# cascadence11.net
KiCad netlist of a schematic drawn in EAGLE
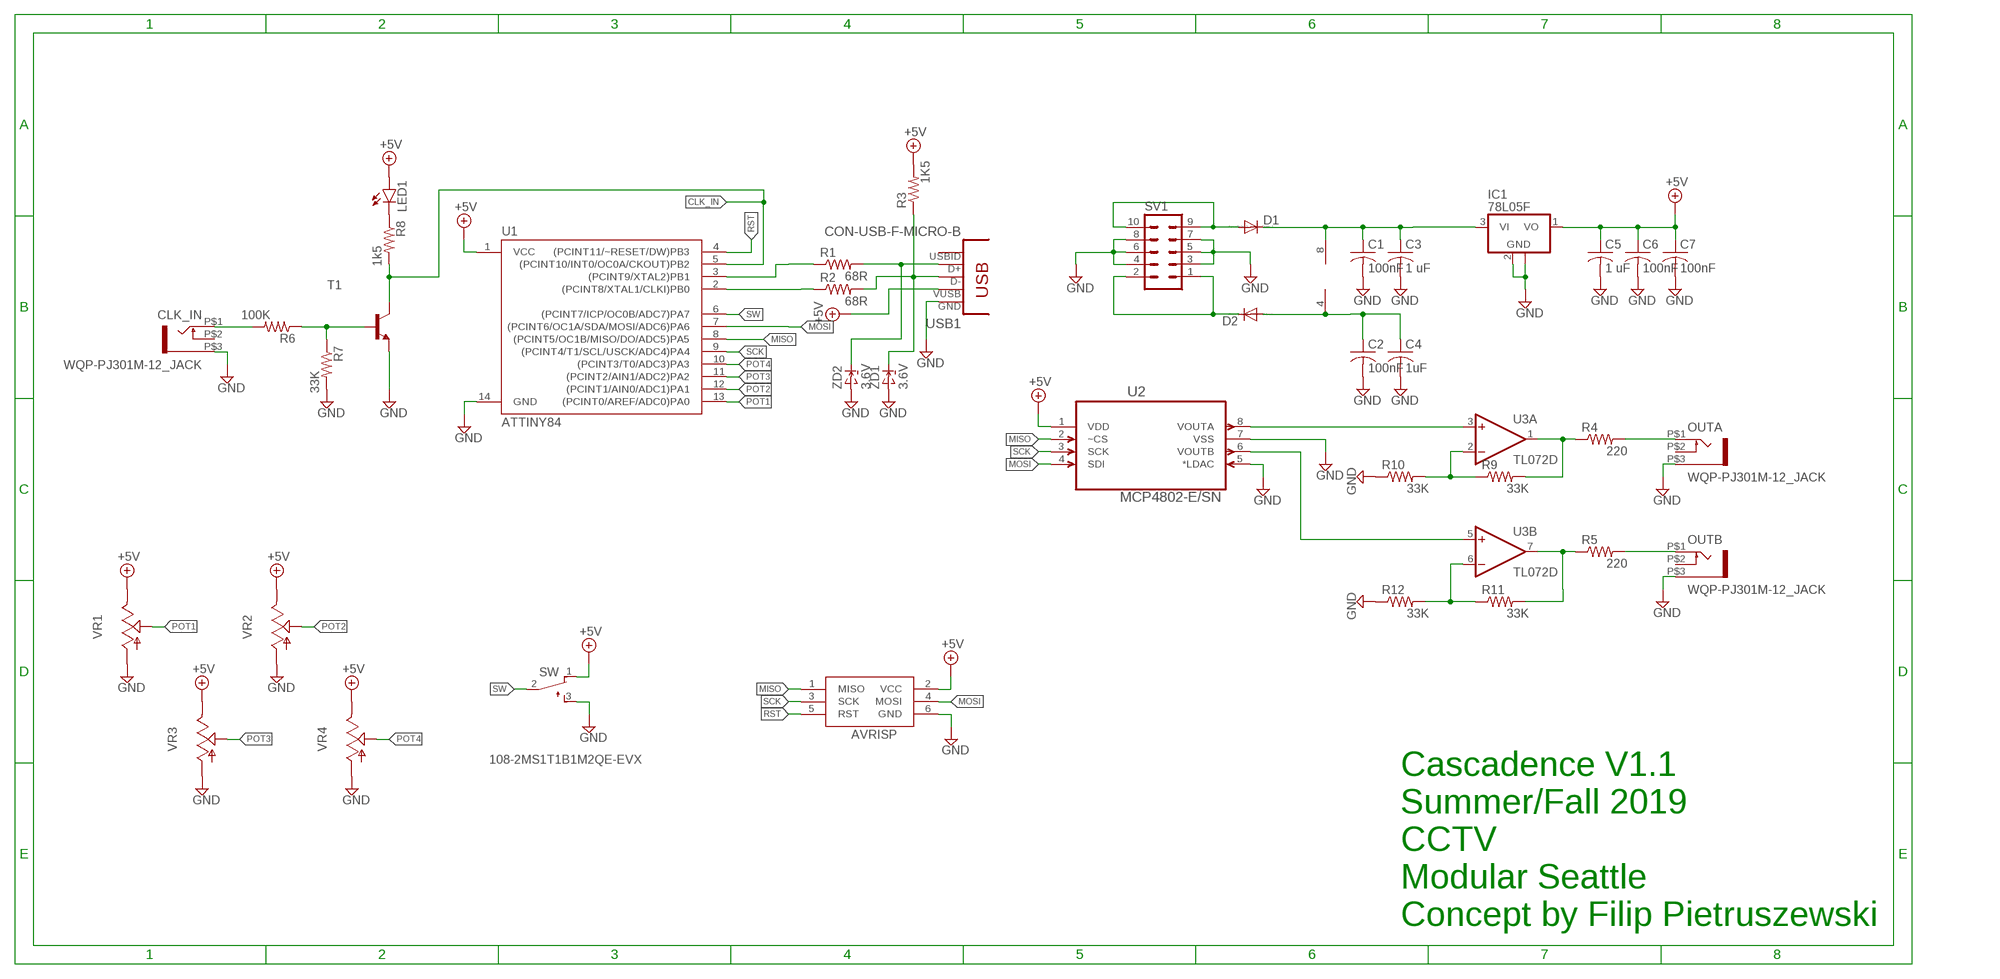
[diagram p0: schematic, sheet 1]

(export (version "E")
  (design (tool "Eeschema 10.0.6"))
  (components
    (comp (ref "AVRISP")
      (value "AVRISP-6")
      (footprint "eagle-import:AVRISP")
      (libsource (lib "eagle-import") (part "AVRISP-6"))
    )
    (comp (ref "C1")
      (value "100nF")
      (footprint "eagle-import:C0805K")
      (libsource (lib "eagle-import") (part "C-USC0805K"))
    )
    (comp (ref "C2")
      (value "100nF")
      (footprint "eagle-import:C0805K")
      (libsource (lib "eagle-import") (part "C-USC0805K"))
    )
    (comp (ref "C3")
      (value "1 uF")
      (footprint "eagle-import:C1206")
      (libsource (lib "eagle-import") (part "C-USC1206"))
    )
    (comp (ref "C4")
      (value "1uF")
      (footprint "eagle-import:C1206")
      (libsource (lib "eagle-import") (part "C-USC1206"))
    )
    (comp (ref "C5")
      (value "1 uF")
      (footprint "eagle-import:C1206")
      (libsource (lib "eagle-import") (part "C-USC1206"))
    )
    (comp (ref "C6")
      (value "100nF")
      (footprint "eagle-import:C0805K")
      (libsource (lib "eagle-import") (part "C-USC0805K"))
    )
    (comp (ref "C7")
      (value "100nF")
      (footprint "eagle-import:C0805K")
      (libsource (lib "eagle-import") (part "C-USC0805K"))
    )
    (comp (ref "CLK_IN")
      (value "WQP-PJ301M-12_JACK")
      (footprint "eagle-import:WQP-PJ301M-12_JACK")
      (libsource (lib "eagle-import") (part "WQP-PJ301M-12_JACK"))
    )
    (comp (ref "D1")
      (value "DIODE-SMB")
      (footprint "eagle-import:SMB")
      (libsource (lib "eagle-import") (part "DIODE-SMB"))
    )
    (comp (ref "D2")
      (value "DIODE-SMB")
      (footprint "eagle-import:SMB")
      (libsource (lib "eagle-import") (part "DIODE-SMB"))
    )
    (comp (ref "IC1")
      (value "78L05F")
      (footprint "eagle-import:SOT89")
      (libsource (lib "eagle-import") (part "78LF05"))
    )
    (comp (ref "LED1")
      (value "LED3MM")
      (footprint "eagle-import:LED3MM")
      (libsource (lib "eagle-import") (part "LED3MM"))
    )
    (comp (ref "OUTA")
      (value "WQP-PJ301M-12_JACK")
      (footprint "eagle-import:WQP-PJ301M-12_JACK")
      (libsource (lib "eagle-import") (part "WQP-PJ301M-12_JACK"))
    )
    (comp (ref "OUTB")
      (value "WQP-PJ301M-12_JACK")
      (footprint "eagle-import:WQP-PJ301M-12_JACK")
      (libsource (lib "eagle-import") (part "WQP-PJ301M-12_JACK"))
    )
    (comp (ref "R1")
      (value "68R")
      (footprint "eagle-import:R0805W")
      (libsource (lib "eagle-import") (part "R-US_R0805W"))
    )
    (comp (ref "R2")
      (value "68R")
      (footprint "eagle-import:R0805W")
      (libsource (lib "eagle-import") (part "R-US_R0805W"))
    )
    (comp (ref "R3")
      (value "1K5")
      (footprint "eagle-import:R0805W")
      (libsource (lib "eagle-import") (part "R-US_R0805W"))
    )
    (comp (ref "R4")
      (value "220")
      (footprint "eagle-import:R0805W")
      (libsource (lib "eagle-import") (part "R-US_R0805W"))
    )
    (comp (ref "R5")
      (value "220")
      (footprint "eagle-import:R0805W")
      (libsource (lib "eagle-import") (part "R-US_R0805W"))
    )
    (comp (ref "R6")
      (value "100K")
      (footprint "eagle-import:R0805W")
      (libsource (lib "eagle-import") (part "R-US_R0805W"))
    )
    (comp (ref "R7")
      (value "33K")
      (footprint "eagle-import:R0805W")
      (libsource (lib "eagle-import") (part "R-US_R0805W"))
    )
    (comp (ref "R8")
      (value "1k5")
      (footprint "eagle-import:R0805W")
      (libsource (lib "eagle-import") (part "R-US_R0805W"))
    )
    (comp (ref "R9")
      (value "33K")
      (footprint "eagle-import:R0805W")
      (libsource (lib "eagle-import") (part "R-US_R0805W"))
    )
    (comp (ref "R10")
      (value "33K")
      (footprint "eagle-import:R0805W")
      (libsource (lib "eagle-import") (part "R-US_R0805W"))
    )
    (comp (ref "R11")
      (value "33K")
      (footprint "eagle-import:R0805W")
      (libsource (lib "eagle-import") (part "R-US_R0805W"))
    )
    (comp (ref "R12")
      (value "33K")
      (footprint "eagle-import:R0805W")
      (libsource (lib "eagle-import") (part "R-US_R0805W"))
    )
    (comp (ref "SV1")
      (value "EURO_POWER_HEADERFAT_PADS")
      (footprint "eagle-import:EURO_PWR_HEADER_FAT")
      (libsource (lib "eagle-import") (part "EURO_POWER_HEADERFAT_PADS"))
    )
    (comp (ref "SW")
      (value "108-2MS1T1B1M2QE-EVX")
      (footprint "eagle-import:TL3XPO")
      (libsource (lib "eagle-import") (part "TL32PO"))
    )
    (comp (ref "T1")
      (value "MMBT3904LT1-NPN-SOT23-BEC")
      (footprint "eagle-import:SOT23-BEC")
      (libsource (lib "eagle-import") (part "-NPN-SOT23-BECMMBT3904LT1"))
    )
    (comp (ref "U1")
      (value "ATTINY84")
      (footprint "eagle-import:SO14")
      (libsource (lib "eagle-import") (part "ATTINY84"))
    )
    (comp (ref "U2")
      (value "MCP4802-E/SN")
      (footprint "eagle-import:SOIC127P600X175-8N")
      (fields (field (name "MF") "Microchip") (field (name "MP") "MCP4812-E/SN"))
      (libsource (lib "eagle-import") (part "MCP4812-E/SN"))
    )
    (comp (ref "U3")
      (value "TL072D")
      (footprint "eagle-import:SO08")
      (libsource (lib "eagle-import") (part "TL072D"))
    )
    (comp (ref "USB1")
      (value "CON-USB-F-MICRO-B")
      (footprint "eagle-import:CONN_USB_MICRO-B")
      (libsource (lib "eagle-import") (part "CON-USB-F-MICRO-B"))
    )
    (comp (ref "VR1")
      (value "9MM_SNAP-IN_POT_")
      (footprint "eagle-import:9MM_SNAP-IN_POT")
      (libsource (lib "eagle-import") (part "9MM_SNAP-IN_POT_"))
    )
    (comp (ref "VR2")
      (value "9MM_SNAP-IN_POT_")
      (footprint "eagle-import:9MM_SNAP-IN_POT")
      (libsource (lib "eagle-import") (part "9MM_SNAP-IN_POT_"))
    )
    (comp (ref "VR3")
      (value "9MM_SNAP-IN_POT_")
      (footprint "eagle-import:9MM_SNAP-IN_POT")
      (libsource (lib "eagle-import") (part "9MM_SNAP-IN_POT_"))
    )
    (comp (ref "VR4")
      (value "9MM_SNAP-IN_POT_")
      (footprint "eagle-import:9MM_SNAP-IN_POT")
      (libsource (lib "eagle-import") (part "9MM_SNAP-IN_POT_"))
    )
    (comp (ref "ZD1")
      (value "3.6V")
      (footprint "eagle-import:SOD-123")
      (libsource (lib "eagle-import") (part "ZENERSOD-123"))
    )
    (comp (ref "ZD2")
      (value "3.6V")
      (footprint "eagle-import:SOD-123")
      (libsource (lib "eagle-import") (part "ZENERSOD-123"))
    )
  )
  (nets
    (net (code "1") (name "+5V") (class "Default")
      (node (ref "AVRISP") (pin "2") (pinfunction "VCC_2") (pintype "power_in"))
      (node (ref "C5") (pin "1") (pinfunction "1_1") (pintype "passive"))
      (node (ref "C6") (pin "1") (pinfunction "1_1") (pintype "passive"))
      (node (ref "C7") (pin "1") (pinfunction "1_1") (pintype "passive"))
      (node (ref "IC1") (pin "1") (pinfunction "VO_1") (pintype "passive"))
      (node (ref "LED1") (pin "A") (pinfunction "A_A") (pintype "passive"))
      (node (ref "R3") (pin "2") (pinfunction "2_2") (pintype "passive"))
      (node (ref "SW") (pin "1") (pinfunction "O_1") (pintype "passive"))
      (node (ref "U1") (pin "1") (pinfunction "VCC_1") (pintype "bidirectional"))
      (node (ref "U2") (pin "1") (pinfunction "VDD_1") (pintype "power_in"))
      (node (ref "USB1") (pin "P1") (pinfunction "VUSB_P1") (pintype "bidirectional"))
      (node (ref "VR1") (pin "3") (pinfunction "E_3") (pintype "passive"))
      (node (ref "VR2") (pin "3") (pinfunction "E_3") (pintype "passive"))
      (node (ref "VR3") (pin "3") (pinfunction "E_3") (pintype "passive"))
      (node (ref "VR4") (pin "3") (pinfunction "E_3") (pintype "passive"))
    )
    (net (code "2") (name "CLK_IN") (class "Default")
      (node (ref "R8") (pin "2") (pinfunction "2_2") (pintype "passive"))
      (node (ref "T1") (pin "C") (pinfunction "C_C") (pintype "passive"))
      (node (ref "U1") (pin "5") (pinfunction "(PCINT10/INT0/OC0A/CKOUT)PB2_5") (pintype "bidirectional"))
    )
    (net (code "3") (name "GND") (class "Default")
      (node (ref "AVRISP") (pin "6") (pinfunction "GND_6") (pintype "power_in"))
      (node (ref "C1") (pin "2") (pinfunction "2_2") (pintype "passive"))
      (node (ref "C2") (pin "2") (pinfunction "2_2") (pintype "passive"))
      (node (ref "C3") (pin "2") (pinfunction "2_2") (pintype "passive"))
      (node (ref "C4") (pin "2") (pinfunction "2_2") (pintype "passive"))
      (node (ref "C5") (pin "2") (pinfunction "2_2") (pintype "passive"))
      (node (ref "C6") (pin "2") (pinfunction "2_2") (pintype "passive"))
      (node (ref "C7") (pin "2") (pinfunction "2_2") (pintype "passive"))
      (node (ref "CLK_IN") (pin "P$3") (pinfunction "1_P$3") (pintype "passive"))
      (node (ref "IC1") (pin "2") (pinfunction "GND_2") (pintype "passive"))
      (node (ref "IC1") (pin "2@1") (pinfunction "GND_2@1") (pintype "passive"))
      (node (ref "OUTA") (pin "P$3") (pinfunction "1_P$3") (pintype "passive"))
      (node (ref "OUTB") (pin "P$3") (pinfunction "1_P$3") (pintype "passive"))
      (node (ref "R10") (pin "1") (pinfunction "1_1") (pintype "passive"))
      (node (ref "R12") (pin "1") (pinfunction "1_1") (pintype "passive"))
      (node (ref "R7") (pin "2") (pinfunction "2_2") (pintype "passive"))
      (node (ref "SV1") (pin "3") (pinfunction "3_3") (pintype "passive"))
      (node (ref "SV1") (pin "4") (pinfunction "4_4") (pintype "passive"))
      (node (ref "SV1") (pin "5") (pinfunction "5_5") (pintype "passive"))
      (node (ref "SV1") (pin "6") (pinfunction "6_6") (pintype "passive"))
      (node (ref "SV1") (pin "7") (pinfunction "7_7") (pintype "passive"))
      (node (ref "SV1") (pin "8") (pinfunction "8_8") (pintype "passive"))
      (node (ref "SW") (pin "3") (pinfunction "S_3") (pintype "passive"))
      (node (ref "T1") (pin "E") (pinfunction "E_E") (pintype "passive"))
      (node (ref "U1") (pin "14") (pinfunction "GND_14") (pintype "bidirectional"))
      (node (ref "U2") (pin "5") (pinfunction "*LDAC_5") (pintype "input"))
      (node (ref "U2") (pin "7") (pinfunction "VSS_7") (pintype "power_in"))
      (node (ref "USB1") (pin "P5") (pinfunction "GND_P5") (pintype "bidirectional"))
      (node (ref "VR1") (pin "1") (pinfunction "A_1") (pintype "passive"))
      (node (ref "VR2") (pin "1") (pinfunction "A_1") (pintype "passive"))
      (node (ref "VR3") (pin "1") (pinfunction "A_1") (pintype "passive"))
      (node (ref "VR4") (pin "1") (pinfunction "A_1") (pintype "passive"))
      (node (ref "ZD1") (pin "A") (pinfunction "A_A") (pintype "passive"))
      (node (ref "ZD2") (pin "A") (pinfunction "A_A") (pintype "passive"))
    )
    (net (code "4") (name "MISO") (class "Default")
      (node (ref "AVRISP") (pin "1") (pinfunction "MISO_1") (pintype "input"))
      (node (ref "U1") (pin "8") (pinfunction "(PCINT5/OC1B/MISO/DO/ADC5)PA5_8") (pintype "bidirectional"))
      (node (ref "U2") (pin "2") (pinfunction "~{CS}_2") (pintype "input"))
    )
    (net (code "5") (name "MOSI") (class "Default")
      (node (ref "AVRISP") (pin "4") (pinfunction "MOSI_4") (pintype "output"))
      (node (ref "U1") (pin "7") (pinfunction "(PCINT6/OC1A/SDA/MOSI/ADC6)PA6_7") (pintype "bidirectional"))
      (node (ref "U2") (pin "4") (pinfunction "SDI_4") (pintype "input"))
    )
    (net (code "6") (name "Net-(CLK_IN-2)") (class "Default")
      (node (ref "CLK_IN") (pin "P$1") (pinfunction "2_P$1") (pintype "passive"))
      (node (ref "R6") (pin "2") (pinfunction "2_2") (pintype "passive"))
    )
    (net (code "7") (name "Net-(D1-PadA)") (class "Default")
      (node (ref "D1") (pin "A") (pinfunction "A_A") (pintype "passive"))
      (node (ref "SV1") (pin "10") (pinfunction "10_10") (pintype "passive"))
      (node (ref "SV1") (pin "9") (pinfunction "9_9") (pintype "passive"))
    )
    (net (code "8") (name "Net-(D2-PadC)") (class "Default")
      (node (ref "D2") (pin "C") (pinfunction "C_C") (pintype "passive"))
      (node (ref "SV1") (pin "1") (pinfunction "1_1") (pintype "passive"))
      (node (ref "SV1") (pin "2") (pinfunction "2_2") (pintype "passive"))
    )
    (net (code "9") (name "Net-(IC1-VI)") (class "Default")
      (node (ref "C1") (pin "1") (pinfunction "1_1") (pintype "passive"))
      (node (ref "C3") (pin "1") (pinfunction "1_1") (pintype "passive"))
      (node (ref "D1") (pin "C") (pinfunction "C_C") (pintype "passive"))
      (node (ref "IC1") (pin "3") (pinfunction "VI_3") (pintype "input"))
      (node (ref "U3") (pin "8") (pinfunction "V+_8") (pintype "power_in"))
    )
    (net (code "10") (name "Net-(LED1-C)") (class "Default")
      (node (ref "LED1") (pin "K") (pinfunction "C_K") (pintype "passive"))
      (node (ref "R8") (pin "1") (pinfunction "1_1") (pintype "passive"))
    )
    (net (code "11") (name "Net-(OUTA-2)") (class "Default")
      (node (ref "OUTA") (pin "P$1") (pinfunction "2_P$1") (pintype "passive"))
      (node (ref "R4") (pin "2") (pinfunction "2_2") (pintype "passive"))
    )
    (net (code "12") (name "Net-(OUTB-2)") (class "Default")
      (node (ref "OUTB") (pin "P$1") (pinfunction "2_P$1") (pintype "passive"))
      (node (ref "R5") (pin "2") (pinfunction "2_2") (pintype "passive"))
    )
    (net (code "13") (name "Net-(R6-Pad1)") (class "Default")
      (node (ref "R6") (pin "1") (pinfunction "1_1") (pintype "passive"))
      (node (ref "R7") (pin "1") (pinfunction "1_1") (pintype "passive"))
      (node (ref "T1") (pin "B") (pinfunction "B_B") (pintype "passive"))
    )
    (net (code "14") (name "Net-(U1-(PCINT8{slash}XTAL1{slash}CLKI)PB0)") (class "Default")
      (node (ref "R2") (pin "1") (pinfunction "1_1") (pintype "passive"))
      (node (ref "U1") (pin "2") (pinfunction "(PCINT8/XTAL1/CLKI)PB0_2") (pintype "bidirectional"))
    )
    (net (code "15") (name "Net-(U1-(PCINT9{slash}XTAL2)PB1)") (class "Default")
      (node (ref "R1") (pin "1") (pinfunction "1_1") (pintype "passive"))
      (node (ref "U1") (pin "3") (pinfunction "(PCINT9/XTAL2)PB1_3") (pintype "bidirectional"))
    )
    (net (code "16") (name "Net-(U2-VOUTA)") (class "Default")
      (node (ref "U2") (pin "8") (pinfunction "VOUTA_8") (pintype "output"))
      (node (ref "U3") (pin "3") (pinfunction "+IN_3") (pintype "input"))
    )
    (net (code "17") (name "Net-(U2-VOUTB)") (class "Default")
      (node (ref "U2") (pin "6") (pinfunction "VOUTB_6") (pintype "output"))
      (node (ref "U3") (pin "5") (pinfunction "+IN_5") (pintype "input"))
    )
    (net (code "18") (name "Net-(U3A--IN)") (class "Default")
      (node (ref "R10") (pin "2") (pinfunction "2_2") (pintype "passive"))
      (node (ref "R9") (pin "1") (pinfunction "1_1") (pintype "passive"))
      (node (ref "U3") (pin "2") (pinfunction "-IN_2") (pintype "input"))
    )
    (net (code "19") (name "Net-(U3A-OUT)") (class "Default")
      (node (ref "R4") (pin "1") (pinfunction "1_1") (pintype "passive"))
      (node (ref "R9") (pin "2") (pinfunction "2_2") (pintype "passive"))
      (node (ref "U3") (pin "1") (pinfunction "OUT_1") (pintype "output"))
    )
    (net (code "20") (name "Net-(U3B--IN)") (class "Default")
      (node (ref "R11") (pin "1") (pinfunction "1_1") (pintype "passive"))
      (node (ref "R12") (pin "2") (pinfunction "2_2") (pintype "passive"))
      (node (ref "U3") (pin "6") (pinfunction "-IN_6") (pintype "input"))
    )
    (net (code "21") (name "Net-(U3B-OUT)") (class "Default")
      (node (ref "R11") (pin "2") (pinfunction "2_2") (pintype "passive"))
      (node (ref "R5") (pin "1") (pinfunction "1_1") (pintype "passive"))
      (node (ref "U3") (pin "7") (pinfunction "OUT_7") (pintype "output"))
    )
    (net (code "22") (name "Net-(U3C-V-)") (class "Default")
      (node (ref "C2") (pin "1") (pinfunction "1_1") (pintype "passive"))
      (node (ref "C4") (pin "1") (pinfunction "1_1") (pintype "passive"))
      (node (ref "D2") (pin "A") (pinfunction "A_A") (pintype "passive"))
      (node (ref "U3") (pin "4") (pinfunction "V-_4") (pintype "power_in"))
    )
    (net (code "23") (name "Net-(USB1B-D+)") (class "Default")
      (node (ref "R1") (pin "2") (pinfunction "2_2") (pintype "passive"))
      (node (ref "USB1") (pin "P3") (pinfunction "D+_P3") (pintype "bidirectional"))
      (node (ref "ZD2") (pin "C") (pinfunction "C_C") (pintype "passive"))
    )
    (net (code "24") (name "Net-(USB1B-D-)") (class "Default")
      (node (ref "R2") (pin "2") (pinfunction "2_2") (pintype "passive"))
      (node (ref "R3") (pin "1") (pinfunction "1_1") (pintype "passive"))
      (node (ref "USB1") (pin "P2") (pinfunction "D-_P2") (pintype "bidirectional"))
      (node (ref "ZD1") (pin "C") (pinfunction "C_C") (pintype "passive"))
    )
    (net (code "25") (name "POT1") (class "Default")
      (node (ref "U1") (pin "13") (pinfunction "(PCINT0/AREF/ADC0)PA0_13") (pintype "bidirectional"))
      (node (ref "VR1") (pin "2") (pinfunction "S_2") (pintype "passive"))
    )
    (net (code "26") (name "POT2") (class "Default")
      (node (ref "U1") (pin "12") (pinfunction "(PCINT1/AIN0/ADC1)PA1_12") (pintype "bidirectional"))
      (node (ref "VR2") (pin "2") (pinfunction "S_2") (pintype "passive"))
    )
    (net (code "27") (name "POT3") (class "Default")
      (node (ref "U1") (pin "11") (pinfunction "(PCINT2/AIN1/ADC2)PA2_11") (pintype "bidirectional"))
      (node (ref "VR3") (pin "2") (pinfunction "S_2") (pintype "passive"))
    )
    (net (code "28") (name "POT4") (class "Default")
      (node (ref "U1") (pin "10") (pinfunction "(PCINT3/T0/ADC3)PA3_10") (pintype "bidirectional"))
      (node (ref "VR4") (pin "2") (pinfunction "S_2") (pintype "passive"))
    )
    (net (code "29") (name "RST") (class "Default")
      (node (ref "AVRISP") (pin "5") (pinfunction "RST_5") (pintype "output"))
      (node (ref "U1") (pin "4") (pinfunction "(PCINT11/~{RESET/DW})PB3_4") (pintype "bidirectional"))
    )
    (net (code "30") (name "SCK") (class "Default")
      (node (ref "AVRISP") (pin "3") (pinfunction "SCK_3") (pintype "output"))
      (node (ref "U1") (pin "9") (pinfunction "(PCINT4/T1/SCL/USCK/ADC4)PA4_9") (pintype "bidirectional"))
      (node (ref "U2") (pin "3") (pinfunction "SCK_3") (pintype "input"))
    )
    (net (code "31") (name "SW") (class "Default")
      (node (ref "SW") (pin "2") (pinfunction "P_2") (pintype "passive"))
      (node (ref "U1") (pin "6") (pinfunction "(PCINT7/ICP/OC0B/ADC7)PA7_6") (pintype "bidirectional"))
    )
    (net (code "32") (name "unconnected-(CLK_IN-3-PadP$2)") (class "Default")
      (node (ref "CLK_IN") (pin "P$2") (pinfunction "3_P$2") (pintype "passive"))
    )
    (net (code "33") (name "unconnected-(OUTA-3-PadP$2)") (class "Default")
      (node (ref "OUTA") (pin "P$2") (pinfunction "3_P$2") (pintype "passive"))
    )
    (net (code "34") (name "unconnected-(OUTB-3-PadP$2)") (class "Default")
      (node (ref "OUTB") (pin "P$2") (pinfunction "3_P$2") (pintype "passive"))
    )
    (net (code "35") (name "unconnected-(USB1B-USBID-PadP4)") (class "Default")
      (node (ref "USB1") (pin "P4") (pinfunction "USBID_P4") (pintype "bidirectional"))
    )
  )
)
